# MCU_PWR.net
KiCad netlist of a schematic drawn in Altium Designer
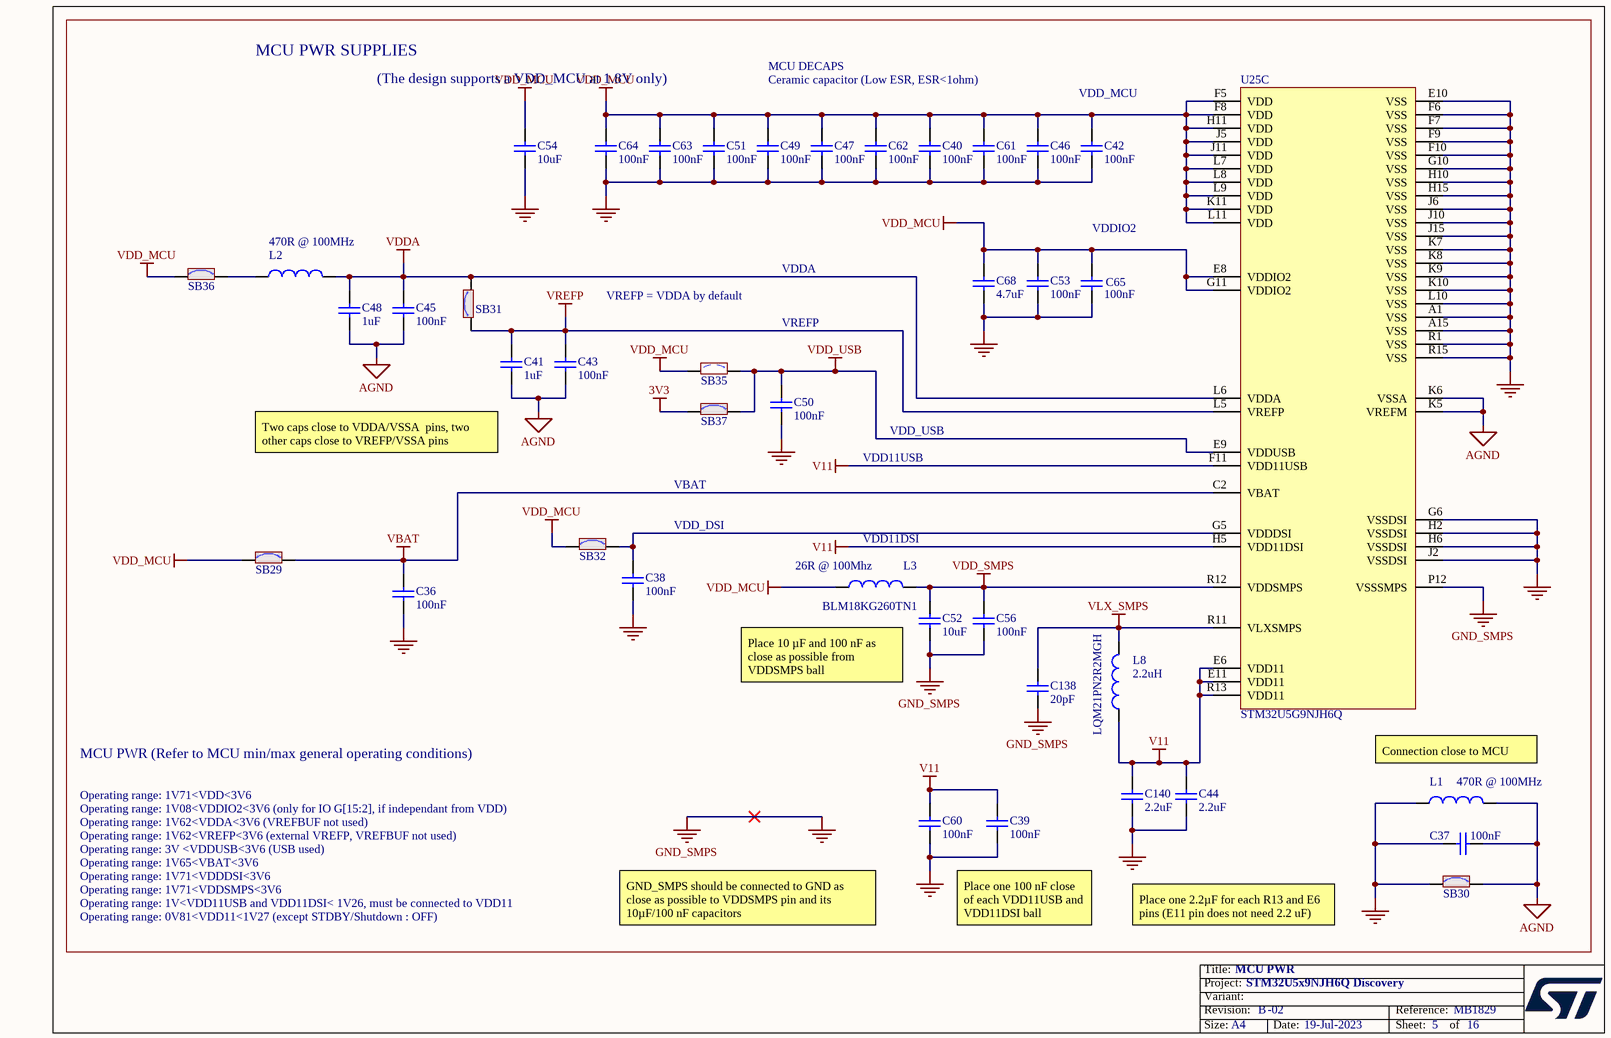
[diagram p0: MCU_PWR.SchDoc]

(export (version "E")
  (design (tool "Eeschema 10.0.6"))
  (components
    (comp (ref "C36")
      (value "100nF")
      (footprint "MCD_PARTS:C0402")
      (description "Capacitor, MLCC, 100nF, 16V, X7R, +/-10%, 0402, T=0.5mm")
      (fields
        (field (name "INTERNAL_PART_NUMBER") "MCD-00006")
        (field (name "MANUFACTURER_PART_NUMBER") "CC0402KRX7R7BB104")
      )
      (libsource (lib "MCD_PARTS_database") (part "Capacitor"))
    )
    (comp (ref "C37")
      (value "100nF")
      (footprint "MCD_PARTS:C0402")
      (description "Capacitor, MLCC, 100nF, 16V, X7R, +/-10%, 0402, T=0.5mm")
      (fields
        (field (name "INTERNAL_PART_NUMBER") "MCD-00006")
        (field (name "MANUFACTURER_PART_NUMBER") "CC0402KRX7R7BB104")
      )
      (libsource (lib "MCD_PARTS_database") (part "Capacitor"))
    )
    (comp (ref "C38")
      (value "100nF")
      (footprint "MCD_PARTS:C0402")
      (description "Capacitor, MLCC, 100nF, 16V, X7R, +/-10%, 0402, T=0.5mm")
      (fields
        (field (name "INTERNAL_PART_NUMBER") "MCD-00006")
        (field (name "MANUFACTURER_PART_NUMBER") "CC0402KRX7R7BB104")
      )
      (libsource (lib "MCD_PARTS_database") (part "Capacitor"))
    )
    (comp (ref "C39")
      (value "100nF")
      (footprint "MCD_PARTS:C0402")
      (description "Capacitor, MLCC, 100nF, 16V, X7R, +/-10%, 0402, T=0.5mm")
      (fields
        (field (name "INTERNAL_PART_NUMBER") "MCD-00006")
        (field (name "MANUFACTURER_PART_NUMBER") "CC0402KRX7R7BB104")
      )
      (libsource (lib "MCD_PARTS_database") (part "Capacitor"))
    )
    (comp (ref "C40")
      (value "100nF")
      (footprint "MCD_PARTS:C0402")
      (description "Capacitor, MLCC, 100nF, 16V, X7R, +/-10%, 0402, T=0.5mm")
      (fields
        (field (name "INTERNAL_PART_NUMBER") "MCD-00006")
        (field (name "MANUFACTURER_PART_NUMBER") "CC0402KRX7R7BB104")
      )
      (libsource (lib "MCD_PARTS_database") (part "Capacitor"))
    )
    (comp (ref "C41")
      (value "1uF")
      (footprint "MCD_PARTS:C0402")
      (description "Capacitor, MLCC, 1uF, 10V, X5R, +/-10%, 0402, T=0.5mm")
      (fields
        (field (name "INTERNAL_PART_NUMBER") "MCD-01722")
        (field (name "MANUFACTURER_PART_NUMBER") "CC0402KRX5R6BB105")
      )
      (libsource (lib "MCD_PARTS_database") (part "Capacitor"))
    )
    (comp (ref "C42")
      (value "100nF")
      (footprint "MCD_PARTS:C0402")
      (description "Capacitor, MLCC, 100nF, 16V, X7R, +/-10%, 0402, T=0.5mm")
      (fields
        (field (name "INTERNAL_PART_NUMBER") "MCD-00006")
        (field (name "MANUFACTURER_PART_NUMBER") "CC0402KRX7R7BB104")
      )
      (libsource (lib "MCD_PARTS_database") (part "Capacitor"))
    )
    (comp (ref "C43")
      (value "100nF")
      (footprint "MCD_PARTS:C0402")
      (description "Capacitor, MLCC, 100nF, 16V, X7R, +/-10%, 0402, T=0.5mm")
      (fields
        (field (name "INTERNAL_PART_NUMBER") "MCD-00006")
        (field (name "MANUFACTURER_PART_NUMBER") "CC0402KRX7R7BB104")
      )
      (libsource (lib "MCD_PARTS_database") (part "Capacitor"))
    )
    (comp (ref "C44")
      (value "2.2uF")
      (footprint "MCD_PARTS:C0402")
      (description "Capacitor, MLCC, 2.2uF, 6.3V, X5R, +/-10%, 0402, T=0.5mm")
      (fields (field (name "INTERNAL_PART_NUMBER") "MCD-02606") (field (name "MANUFACTURER") "YAGEO"))
      (libsource (lib "MCD_PARTS_database") (part "Capacitor"))
    )
    (comp (ref "C45")
      (value "100nF")
      (footprint "MCD_PARTS:C0402")
      (description "Capacitor, MLCC, 100nF, 16V, X7R, +/-10%, 0402, T=0.5mm")
      (fields
        (field (name "INTERNAL_PART_NUMBER") "MCD-00006")
        (field (name "MANUFACTURER_PART_NUMBER") "CC0402KRX7R7BB104")
      )
      (libsource (lib "MCD_PARTS_database") (part "Capacitor"))
    )
    (comp (ref "C46")
      (value "100nF")
      (footprint "MCD_PARTS:C0402")
      (description "Capacitor, MLCC, 100nF, 16V, X7R, +/-10%, 0402, T=0.5mm")
      (fields
        (field (name "INTERNAL_PART_NUMBER") "MCD-00006")
        (field (name "MANUFACTURER_PART_NUMBER") "CC0402KRX7R7BB104")
      )
      (libsource (lib "MCD_PARTS_database") (part "Capacitor"))
    )
    (comp (ref "C47")
      (value "100nF")
      (footprint "MCD_PARTS:C0402")
      (description "Capacitor, MLCC, 100nF, 16V, X7R, +/-10%, 0402, T=0.5mm")
      (fields
        (field (name "INTERNAL_PART_NUMBER") "MCD-00006")
        (field (name "MANUFACTURER_PART_NUMBER") "CC0402KRX7R7BB104")
      )
      (libsource (lib "MCD_PARTS_database") (part "Capacitor"))
    )
    (comp (ref "C48")
      (value "1uF")
      (footprint "MCD_PARTS:C0402")
      (description "Capacitor, MLCC, 1uF, 10V, X5R, +/-10%, 0402, T=0.5mm")
      (fields
        (field (name "INTERNAL_PART_NUMBER") "MCD-01722")
        (field (name "MANUFACTURER_PART_NUMBER") "CC0402KRX5R6BB105")
      )
      (libsource (lib "MCD_PARTS_database") (part "Capacitor"))
    )
    (comp (ref "C49")
      (value "100nF")
      (footprint "MCD_PARTS:C0402")
      (description "Capacitor, MLCC, 100nF, 16V, X7R, +/-10%, 0402, T=0.5mm")
      (fields
        (field (name "INTERNAL_PART_NUMBER") "MCD-00006")
        (field (name "MANUFACTURER_PART_NUMBER") "CC0402KRX7R7BB104")
      )
      (libsource (lib "MCD_PARTS_database") (part "Capacitor"))
    )
    (comp (ref "C50")
      (value "100nF")
      (footprint "MCD_PARTS:C0402")
      (description "Capacitor, MLCC, 100nF, 16V, X7R, +/-10%, 0402, T=0.5mm")
      (fields
        (field (name "INTERNAL_PART_NUMBER") "MCD-00006")
        (field (name "MANUFACTURER_PART_NUMBER") "CC0402KRX7R7BB104")
      )
      (libsource (lib "MCD_PARTS_database") (part "Capacitor"))
    )
    (comp (ref "C51")
      (value "100nF")
      (footprint "MCD_PARTS:C0402")
      (description "Capacitor, MLCC, 100nF, 16V, X7R, +/-10%, 0402, T=0.5mm")
      (fields
        (field (name "INTERNAL_PART_NUMBER") "MCD-00006")
        (field (name "MANUFACTURER_PART_NUMBER") "CC0402KRX7R7BB104")
      )
      (libsource (lib "MCD_PARTS_database") (part "Capacitor"))
    )
    (comp (ref "C52")
      (value "10uF")
      (footprint "MCD_PARTS:C0603_H0P8")
      (description "Capacitor, MLCC, 10uF, 10V, X5R, +/-10%, 0603, T=0.8mm")
      (fields (field (name "INTERNAL_PART_NUMBER") "MCD-02605") (field (name "MANUFACTURER") "YAGEO"))
      (libsource (lib "MCD_PARTS_database") (part "Capacitor"))
    )
    (comp (ref "C53")
      (value "100nF")
      (footprint "MCD_PARTS:C0402")
      (description "Capacitor, MLCC, 100nF, 16V, X7R, +/-10%, 0402, T=0.5mm")
      (fields
        (field (name "INTERNAL_PART_NUMBER") "MCD-00006")
        (field (name "MANUFACTURER_PART_NUMBER") "CC0402KRX7R7BB104")
      )
      (libsource (lib "MCD_PARTS_database") (part "Capacitor"))
    )
    (comp (ref "C54")
      (value "10uF")
      (footprint "MCD_PARTS:C0402")
      (description "Capacitor, MLCC, 10uF, 6V3, X5R, +/-20%, 0402, T=0.5mm")
      (fields (field (name "INTERNAL_PART_NUMBER") "MCD-01716") (field (name "MANUFACTURER") "YAGEO"))
      (libsource (lib "MCD_PARTS_database") (part "Capacitor"))
    )
    (comp (ref "C56")
      (value "100nF")
      (footprint "MCD_PARTS:C0402")
      (description "Capacitor, MLCC, 100nF, 16V, X7R, +/-10%, 0402, T=0.5mm")
      (fields
        (field (name "INTERNAL_PART_NUMBER") "MCD-00006")
        (field (name "MANUFACTURER_PART_NUMBER") "CC0402KRX7R7BB104")
      )
      (libsource (lib "MCD_PARTS_database") (part "Capacitor"))
    )
    (comp (ref "C60")
      (value "100nF")
      (footprint "MCD_PARTS:C0402")
      (description "Capacitor, MLCC, 100nF, 16V, X7R, +/-10%, 0402, T=0.5mm")
      (fields
        (field (name "INTERNAL_PART_NUMBER") "MCD-00006")
        (field (name "MANUFACTURER_PART_NUMBER") "CC0402KRX7R7BB104")
      )
      (libsource (lib "MCD_PARTS_database") (part "Capacitor"))
    )
    (comp (ref "C61")
      (value "100nF")
      (footprint "MCD_PARTS:C0402")
      (description "Capacitor, MLCC, 100nF, 16V, X7R, +/-10%, 0402, T=0.5mm")
      (fields
        (field (name "INTERNAL_PART_NUMBER") "MCD-00006")
        (field (name "MANUFACTURER_PART_NUMBER") "CC0402KRX7R7BB104")
      )
      (libsource (lib "MCD_PARTS_database") (part "Capacitor"))
    )
    (comp (ref "C62")
      (value "100nF")
      (footprint "MCD_PARTS:C0402")
      (description "Capacitor, MLCC, 100nF, 16V, X7R, +/-10%, 0402, T=0.5mm")
      (fields
        (field (name "INTERNAL_PART_NUMBER") "MCD-00006")
        (field (name "MANUFACTURER_PART_NUMBER") "CC0402KRX7R7BB104")
      )
      (libsource (lib "MCD_PARTS_database") (part "Capacitor"))
    )
    (comp (ref "C63")
      (value "100nF")
      (footprint "MCD_PARTS:C0402")
      (description "Capacitor, MLCC, 100nF, 16V, X7R, +/-10%, 0402, T=0.5mm")
      (fields
        (field (name "INTERNAL_PART_NUMBER") "MCD-00006")
        (field (name "MANUFACTURER_PART_NUMBER") "CC0402KRX7R7BB104")
      )
      (libsource (lib "MCD_PARTS_database") (part "Capacitor"))
    )
    (comp (ref "C64")
      (value "100nF")
      (footprint "MCD_PARTS:C0402")
      (description "Capacitor, MLCC, 100nF, 16V, X7R, +/-10%, 0402, T=0.5mm")
      (fields
        (field (name "INTERNAL_PART_NUMBER") "MCD-00006")
        (field (name "MANUFACTURER_PART_NUMBER") "CC0402KRX7R7BB104")
      )
      (libsource (lib "MCD_PARTS_database") (part "Capacitor"))
    )
    (comp (ref "C65")
      (value "100nF")
      (footprint "MCD_PARTS:C0402")
      (description "Capacitor, MLCC, 100nF, 16V, X7R, +/-10%, 0402, T=0.5mm")
      (fields
        (field (name "INTERNAL_PART_NUMBER") "MCD-00006")
        (field (name "MANUFACTURER_PART_NUMBER") "CC0402KRX7R7BB104")
      )
      (libsource (lib "MCD_PARTS_database") (part "Capacitor"))
    )
    (comp (ref "C68")
      (value "4.7uF")
      (footprint "MCD_PARTS:C0402")
      (description "Capacitor, MLCC, 4.7uF, 6.3V, X5R, +/-10%, 0402, T=0.5mm")
      (fields (field (name "INTERNAL_PART_NUMBER") "MCD-02608") (field (name "MANUFACTURER") "YAGEO"))
      (libsource (lib "MCD_PARTS_database") (part "Capacitor"))
    )
    (comp (ref "C138")
      (value "20pF")
      (footprint "MCD_PARTS:C0402")
      (description "Capacitor, MLCC, 20pF, 50V, NPO, +/- 5%, 0402, T=0.5mm")
      (fields (field (name "INTERNAL_PART_NUMBER") "MCD-00016") (field (name "MANUFACTURER") "YAGEO"))
      (libsource (lib "MCD_PARTS_database") (part "Capacitor"))
    )
    (comp (ref "C140")
      (value "2.2uF")
      (footprint "MCD_PARTS:C0402")
      (description "Capacitor, MLCC, 2.2uF, 6.3V, X5R, +/-10%, 0402, T=0.5mm")
      (fields (field (name "INTERNAL_PART_NUMBER") "MCD-02606") (field (name "MANUFACTURER") "YAGEO"))
      (libsource (lib "MCD_PARTS_database") (part "Capacitor"))
    )
    (comp (ref "L1")
      (value "470R @ 100MHz")
      (footprint "MCD_PARTS:IND_0402_MURATA_BLM15H_H0P5")
      (description "Ferrite bead, 470R @ 100MHz, +/-25%, 200mA, 0R6, 0402, T=0.55mm")
      (fields
        (field (name "INTERNAL_PART_NUMBER") "MCD-01986")
        (field (name "MANUFACTURER_PART_NUMBER") "BLM15BD471SN1D")
      )
      (libsource (lib "MCD_PARTS_database") (part "Inductor"))
    )
    (comp (ref "L2")
      (value "470R @ 100MHz")
      (footprint "MCD_PARTS:IND_0402_MURATA_BLM15H_H0P5")
      (description "Ferrite bead, 470R @ 100MHz, +/-25%, 200mA, 0R6, 0402, T=0.55mm")
      (fields
        (field (name "INTERNAL_PART_NUMBER") "MCD-01986")
        (field (name "MANUFACTURER_PART_NUMBER") "BLM15BD471SN1D")
      )
      (libsource (lib "MCD_PARTS_database") (part "Inductor"))
    )
    (comp (ref "L3")
      (value "26R @ 100Mhz")
      (footprint "MCD_PARTS:FIL_0603_H0P65")
      (description "Ferrite bead, 26R @ 100Mhz, +/-25%, 6000mA, 0R007, 0603, T=0.75mm")
      (fields
        (field (name "INTERNAL_PART_NUMBER") "MCD-00305")
        (field (name "MANUFACTURER") "MURATA")
        (field (name "MANUFACTURER_PART_NUMBER") "BLM18KG260TN1")
      )
      (libsource (lib "MCD_PARTS_database") (part "BEAD"))
    )
    (comp (ref "L8")
      (value "2.2uH")
      (footprint "MCD_PARTS:L0805_H0P9")
      (description "Inductor, 2.2uH, +/-20%, 0.7A, 0R156, 0805, T=0.9mm")
      (fields
        (field (name "INTERNAL_PART_NUMBER") "MCD-01060")
        (field (name "MANUFACTURER") "MURATA")
        (field (name "MANUFACTURER_PART_NUMBER") "LQM21PN2R2MGH")
      )
      (libsource (lib "MCD_PARTS_database") (part "Inductor"))
    )
    (comp (ref "SB29")
      (value "SB_ON")
      (footprint "MCD_PARTS:SOLDER-BRIDGE_R0402-0R")
      (description "Solder Bridge 0402 ON")
      (fields
        (field (name "INTERNAL_PART_NUMBER") "MCD-01618")
        (field (name "MANUFACTURER_PART_NUMBER") "RC0402JR-070RL")
      )
      (libsource (lib "MCD_PARTS_database") (part "SB_ON"))
    )
    (comp (ref "SB30")
      (value "SB_ON")
      (footprint "MCD_PARTS:SOLDER-BRIDGE_R0402-0R")
      (description "Solder Bridge 0402 ON")
      (fields
        (field (name "INTERNAL_PART_NUMBER") "MCD-01618")
        (field (name "MANUFACTURER_PART_NUMBER") "RC0402JR-070RL")
      )
      (libsource (lib "MCD_PARTS_database") (part "SB_ON"))
    )
    (comp (ref "SB31")
      (value "SB_ON")
      (footprint "MCD_PARTS:SOLDER-BRIDGE_R0402-0R")
      (description "Solder Bridge 0402 ON")
      (fields
        (field (name "INTERNAL_PART_NUMBER") "MCD-01618")
        (field (name "MANUFACTURER_PART_NUMBER") "RC0402JR-070RL")
      )
      (libsource (lib "") (part "SB_ON_1"))
    )
    (comp (ref "SB32")
      (value "SB_ON")
      (footprint "MCD_PARTS:SOLDER-BRIDGE_R0402-0R")
      (description "Solder Bridge 0402 ON")
      (fields
        (field (name "INTERNAL_PART_NUMBER") "MCD-01618")
        (field (name "MANUFACTURER_PART_NUMBER") "RC0402JR-070RL")
      )
      (libsource (lib "MCD_PARTS_database") (part "SB_ON"))
    )
    (comp (ref "SB35")
      (value "SB_OFF")
      (footprint "MCD_PARTS:SOLDER-BRIDGE_R0402-0R")
      (description "Solder Bridge 0402 OFF")
      (fields
        (field (name "INTERNAL_PART_NUMBER") "MCD-02162")
        (field (name "MANUFACTURER_PART_NUMBER") "RC0402JR-070RL")
      )
      (libsource (lib "MCD_PARTS_database") (part "SB_OFF"))
    )
    (comp (ref "SB36")
      (value "SB_ON")
      (footprint "MCD_PARTS:SOLDER-BRIDGE_R0402-0R")
      (description "Solder Bridge 0402 ON")
      (fields
        (field (name "INTERNAL_PART_NUMBER") "MCD-01618")
        (field (name "MANUFACTURER_PART_NUMBER") "RC0402JR-070RL")
      )
      (libsource (lib "MCD_PARTS_database") (part "SB_ON"))
    )
    (comp (ref "SB37")
      (value "SB_ON")
      (footprint "MCD_PARTS:SOLDER-BRIDGE_R0402-0R")
      (description "Solder Bridge 0402 ON")
      (fields
        (field (name "INTERNAL_PART_NUMBER") "MCD-01618")
        (field (name "MANUFACTURER_PART_NUMBER") "RC0402JR-070RL")
      )
      (libsource (lib "MCD_PARTS_database") (part "SB_ON"))
    )
    (comp (ref "U25")
      (value "STM32U5G9NJH6Q")
      (footprint "ICC_TFBGA216_13X13_P080_H1P10_CODE-A0L2")
      (description "MCU, ARM Cortex-M33, 4MB Flash, 3MB RAM, With Crypto")
      (fields
        (field (name "INTERNAL_PART_NUMBER") "MCD-03271")
        (field (name "MANUFACTURER") "STMICROELECTRONICS")
      )
      (libsource (lib "MCD_PARTS_database") (part "STM32U599NJH6Q_BGA216_SMPS"))
    )
  )
  (nets
    (net (code "1") (name "3V3") (class "Default")
      (node (ref "SB37") (pin "1") (pinfunction "1_1") (pintype "passive"))
    )
    (net (code "2") (name "AGND") (class "Default")
      (node (ref "C37") (pin "2") (pinfunction "2_2") (pintype "passive"))
      (node (ref "C41") (pin "1") (pinfunction "1_1") (pintype "passive"))
      (node (ref "C43") (pin "1") (pinfunction "1_1") (pintype "passive"))
      (node (ref "C45") (pin "1") (pinfunction "1_1") (pintype "passive"))
      (node (ref "C48") (pin "1") (pinfunction "1_1") (pintype "passive"))
      (node (ref "L1") (pin "2") (pinfunction "2_2") (pintype "passive"))
      (node (ref "SB30") (pin "2") (pinfunction "2_2") (pintype "passive"))
      (node (ref "U25") (pin "K5") (pinfunction "VREFM_K5") (pintype "passive"))
      (node (ref "U25") (pin "K6") (pinfunction "VSSA_K6") (pintype "passive"))
    )
    (net (code "3") (name "GND") (class "Default")
      (node (ref "C138") (pin "1") (pinfunction "1_1") (pintype "passive"))
      (node (ref "C140") (pin "1") (pinfunction "1_1") (pintype "passive"))
      (node (ref "C36") (pin "1") (pinfunction "1_1") (pintype "passive"))
      (node (ref "C37") (pin "1") (pinfunction "1_1") (pintype "passive"))
      (node (ref "C38") (pin "1") (pinfunction "1_1") (pintype "passive"))
      (node (ref "C39") (pin "1") (pinfunction "1_1") (pintype "passive"))
      (node (ref "C40") (pin "1") (pinfunction "1_1") (pintype "passive"))
      (node (ref "C42") (pin "1") (pinfunction "1_1") (pintype "passive"))
      (node (ref "C44") (pin "1") (pinfunction "1_1") (pintype "passive"))
      (node (ref "C46") (pin "1") (pinfunction "1_1") (pintype "passive"))
      (node (ref "C47") (pin "1") (pinfunction "1_1") (pintype "passive"))
      (node (ref "C49") (pin "1") (pinfunction "1_1") (pintype "passive"))
      (node (ref "C50") (pin "1") (pinfunction "1_1") (pintype "passive"))
      (node (ref "C51") (pin "1") (pinfunction "1_1") (pintype "passive"))
      (node (ref "C52") (pin "1") (pinfunction "1_1") (pintype "passive"))
      (node (ref "C53") (pin "1") (pinfunction "1_1") (pintype "passive"))
      (node (ref "C54") (pin "1") (pinfunction "1_1") (pintype "passive"))
      (node (ref "C56") (pin "1") (pinfunction "1_1") (pintype "passive"))
      (node (ref "C60") (pin "1") (pinfunction "1_1") (pintype "passive"))
      (node (ref "C61") (pin "1") (pinfunction "1_1") (pintype "passive"))
      (node (ref "C62") (pin "1") (pinfunction "1_1") (pintype "passive"))
      (node (ref "C63") (pin "1") (pinfunction "1_1") (pintype "passive"))
      (node (ref "C64") (pin "1") (pinfunction "1_1") (pintype "passive"))
      (node (ref "C65") (pin "1") (pinfunction "1_1") (pintype "passive"))
      (node (ref "C68") (pin "1") (pinfunction "1_1") (pintype "passive"))
      (node (ref "L1") (pin "1") (pinfunction "1_1") (pintype "passive"))
      (node (ref "SB30") (pin "1") (pinfunction "1_1") (pintype "passive"))
      (node (ref "U25") (pin "A1") (pinfunction "VSS_A1") (pintype "passive"))
      (node (ref "U25") (pin "A15") (pinfunction "VSS_A15") (pintype "passive"))
      (node (ref "U25") (pin "E10") (pinfunction "VSS_E10") (pintype "passive"))
      (node (ref "U25") (pin "F10") (pinfunction "VSS_F10") (pintype "passive"))
      (node (ref "U25") (pin "F6") (pinfunction "VSS_F6") (pintype "passive"))
      (node (ref "U25") (pin "F7") (pinfunction "VSS_F7") (pintype "passive"))
      (node (ref "U25") (pin "F9") (pinfunction "VSS_F9") (pintype "passive"))
      (node (ref "U25") (pin "G10") (pinfunction "VSS_G10") (pintype "passive"))
      (node (ref "U25") (pin "G6") (pinfunction "VSSDSI_G6") (pintype "passive"))
      (node (ref "U25") (pin "H10") (pinfunction "VSS_H10") (pintype "passive"))
      (node (ref "U25") (pin "H15") (pinfunction "VSS_H15") (pintype "passive"))
      (node (ref "U25") (pin "H2") (pinfunction "VSSDSI_H2") (pintype "passive"))
      (node (ref "U25") (pin "H6") (pinfunction "VSSDSI_H6") (pintype "passive"))
      (node (ref "U25") (pin "J10") (pinfunction "VSS_J10") (pintype "passive"))
      (node (ref "U25") (pin "J15") (pinfunction "VSS_J15") (pintype "passive"))
      (node (ref "U25") (pin "J2") (pinfunction "VSSDSI_J2") (pintype "passive"))
      (node (ref "U25") (pin "J6") (pinfunction "VSS_J6") (pintype "passive"))
      (node (ref "U25") (pin "K10") (pinfunction "VSS_K10") (pintype "passive"))
      (node (ref "U25") (pin "K7") (pinfunction "VSS_K7") (pintype "passive"))
      (node (ref "U25") (pin "K8") (pinfunction "VSS_K8") (pintype "passive"))
      (node (ref "U25") (pin "K9") (pinfunction "VSS_K9") (pintype "passive"))
      (node (ref "U25") (pin "L10") (pinfunction "VSS_L10") (pintype "passive"))
      (node (ref "U25") (pin "P12") (pinfunction "VSSSMPS_P12") (pintype "passive"))
      (node (ref "U25") (pin "R1") (pinfunction "VSS_R1") (pintype "passive"))
      (node (ref "U25") (pin "R15") (pinfunction "VSS_R15") (pintype "passive"))
    )
    (net (code "4") (name "Net-(L2-Pad1)") (class "Default")
      (node (ref "L2") (pin "1") (pinfunction "1_1") (pintype "passive"))
      (node (ref "SB36") (pin "2") (pinfunction "2_2") (pintype "passive"))
    )
    (net (code "5") (name "Net-(U25C-VDDDSI)") (class "Default")
      (node (ref "C38") (pin "2") (pinfunction "2_2") (pintype "passive"))
      (node (ref "SB32") (pin "2") (pinfunction "2_2") (pintype "passive"))
      (node (ref "U25") (pin "G5") (pinfunction "VDDDSI_G5") (pintype "passive"))
    )
    (net (code "6") (name "V11") (class "Default")
      (node (ref "C140") (pin "2") (pinfunction "2_2") (pintype "passive"))
      (node (ref "C39") (pin "2") (pinfunction "2_2") (pintype "passive"))
      (node (ref "C44") (pin "2") (pinfunction "2_2") (pintype "passive"))
      (node (ref "C60") (pin "2") (pinfunction "2_2") (pintype "passive"))
      (node (ref "L8") (pin "1") (pinfunction "1_1") (pintype "passive"))
      (node (ref "U25") (pin "E11") (pinfunction "VDD11_E11") (pintype "passive"))
      (node (ref "U25") (pin "E6") (pinfunction "VDD11_E6") (pintype "passive"))
      (node (ref "U25") (pin "F11") (pinfunction "VDD11USB_F11") (pintype "passive"))
      (node (ref "U25") (pin "H5") (pinfunction "VDD11DSI_H5") (pintype "passive"))
      (node (ref "U25") (pin "R13") (pinfunction "VDD11_R13") (pintype "passive"))
    )
    (net (code "7") (name "VBAT") (class "Default")
      (node (ref "C36") (pin "2") (pinfunction "2_2") (pintype "passive"))
      (node (ref "SB29") (pin "2") (pinfunction "2_2") (pintype "passive"))
      (node (ref "U25") (pin "C2") (pinfunction "VBAT_C2") (pintype "passive"))
    )
    (net (code "8") (name "VDDA") (class "Default")
      (node (ref "C45") (pin "2") (pinfunction "2_2") (pintype "passive"))
      (node (ref "C48") (pin "2") (pinfunction "2_2") (pintype "passive"))
      (node (ref "L2") (pin "2") (pinfunction "2_2") (pintype "passive"))
      (node (ref "SB31") (pin "2") (pinfunction "2_2") (pintype "passive"))
      (node (ref "U25") (pin "L6") (pinfunction "VDDA_L6") (pintype "passive"))
    )
    (net (code "9") (name "VDD_MCU") (class "Default")
      (node (ref "C40") (pin "2") (pinfunction "2_2") (pintype "passive"))
      (node (ref "C42") (pin "2") (pinfunction "2_2") (pintype "passive"))
      (node (ref "C46") (pin "2") (pinfunction "2_2") (pintype "passive"))
      (node (ref "C47") (pin "2") (pinfunction "2_2") (pintype "passive"))
      (node (ref "C49") (pin "2") (pinfunction "2_2") (pintype "passive"))
      (node (ref "C51") (pin "2") (pinfunction "2_2") (pintype "passive"))
      (node (ref "C53") (pin "2") (pinfunction "2_2") (pintype "passive"))
      (node (ref "C54") (pin "2") (pinfunction "2_2") (pintype "passive"))
      (node (ref "C61") (pin "2") (pinfunction "2_2") (pintype "passive"))
      (node (ref "C62") (pin "2") (pinfunction "2_2") (pintype "passive"))
      (node (ref "C63") (pin "2") (pinfunction "2_2") (pintype "passive"))
      (node (ref "C64") (pin "2") (pinfunction "2_2") (pintype "passive"))
      (node (ref "C65") (pin "2") (pinfunction "2_2") (pintype "passive"))
      (node (ref "C68") (pin "2") (pinfunction "2_2") (pintype "passive"))
      (node (ref "L3") (pin "1") (pinfunction "1_1") (pintype "passive"))
      (node (ref "SB29") (pin "1") (pinfunction "1_1") (pintype "passive"))
      (node (ref "SB32") (pin "1") (pinfunction "1_1") (pintype "passive"))
      (node (ref "SB35") (pin "1") (pinfunction "1_1") (pintype "passive"))
      (node (ref "SB36") (pin "1") (pinfunction "1_1") (pintype "passive"))
      (node (ref "U25") (pin "E8") (pinfunction "VDDIO2_E8") (pintype "passive"))
      (node (ref "U25") (pin "F5") (pinfunction "VDD_F5") (pintype "passive"))
      (node (ref "U25") (pin "F8") (pinfunction "VDD_F8") (pintype "passive"))
      (node (ref "U25") (pin "G11") (pinfunction "VDDIO2_G11") (pintype "passive"))
      (node (ref "U25") (pin "H11") (pinfunction "VDD_H11") (pintype "passive"))
      (node (ref "U25") (pin "J11") (pinfunction "VDD_J11") (pintype "passive"))
      (node (ref "U25") (pin "J5") (pinfunction "VDD_J5") (pintype "passive"))
      (node (ref "U25") (pin "K11") (pinfunction "VDD_K11") (pintype "passive"))
      (node (ref "U25") (pin "L11") (pinfunction "VDD_L11") (pintype "passive"))
      (node (ref "U25") (pin "L7") (pinfunction "VDD_L7") (pintype "passive"))
      (node (ref "U25") (pin "L8") (pinfunction "VDD_L8") (pintype "passive"))
      (node (ref "U25") (pin "L9") (pinfunction "VDD_L9") (pintype "passive"))
    )
    (net (code "10") (name "VDD_SMPS") (class "Default")
      (node (ref "C52") (pin "2") (pinfunction "2_2") (pintype "passive"))
      (node (ref "C56") (pin "2") (pinfunction "2_2") (pintype "passive"))
      (node (ref "L3") (pin "2") (pinfunction "2_2") (pintype "passive"))
      (node (ref "U25") (pin "R12") (pinfunction "VDDSMPS_R12") (pintype "passive"))
    )
    (net (code "11") (name "VDD_USB") (class "Default")
      (node (ref "C50") (pin "2") (pinfunction "2_2") (pintype "passive"))
      (node (ref "SB35") (pin "2") (pinfunction "2_2") (pintype "passive"))
      (node (ref "SB37") (pin "2") (pinfunction "2_2") (pintype "passive"))
      (node (ref "U25") (pin "E9") (pinfunction "VDDUSB_E9") (pintype "passive"))
    )
    (net (code "12") (name "VLX_SMPS") (class "Default")
      (node (ref "C138") (pin "2") (pinfunction "2_2") (pintype "passive"))
      (node (ref "L8") (pin "2") (pinfunction "2_2") (pintype "passive"))
      (node (ref "U25") (pin "R11") (pinfunction "VLXSMPS_R11") (pintype "passive"))
    )
    (net (code "13") (name "VREFP") (class "Default")
      (node (ref "C41") (pin "2") (pinfunction "2_2") (pintype "passive"))
      (node (ref "C43") (pin "2") (pinfunction "2_2") (pintype "passive"))
      (node (ref "SB31") (pin "1") (pinfunction "1_1") (pintype "passive"))
      (node (ref "U25") (pin "L5") (pinfunction "VREFP_L5") (pintype "passive"))
    )
  )
)
